# 05_BATTERY.net
KiCad netlist of a schematic drawn in Altium Designer
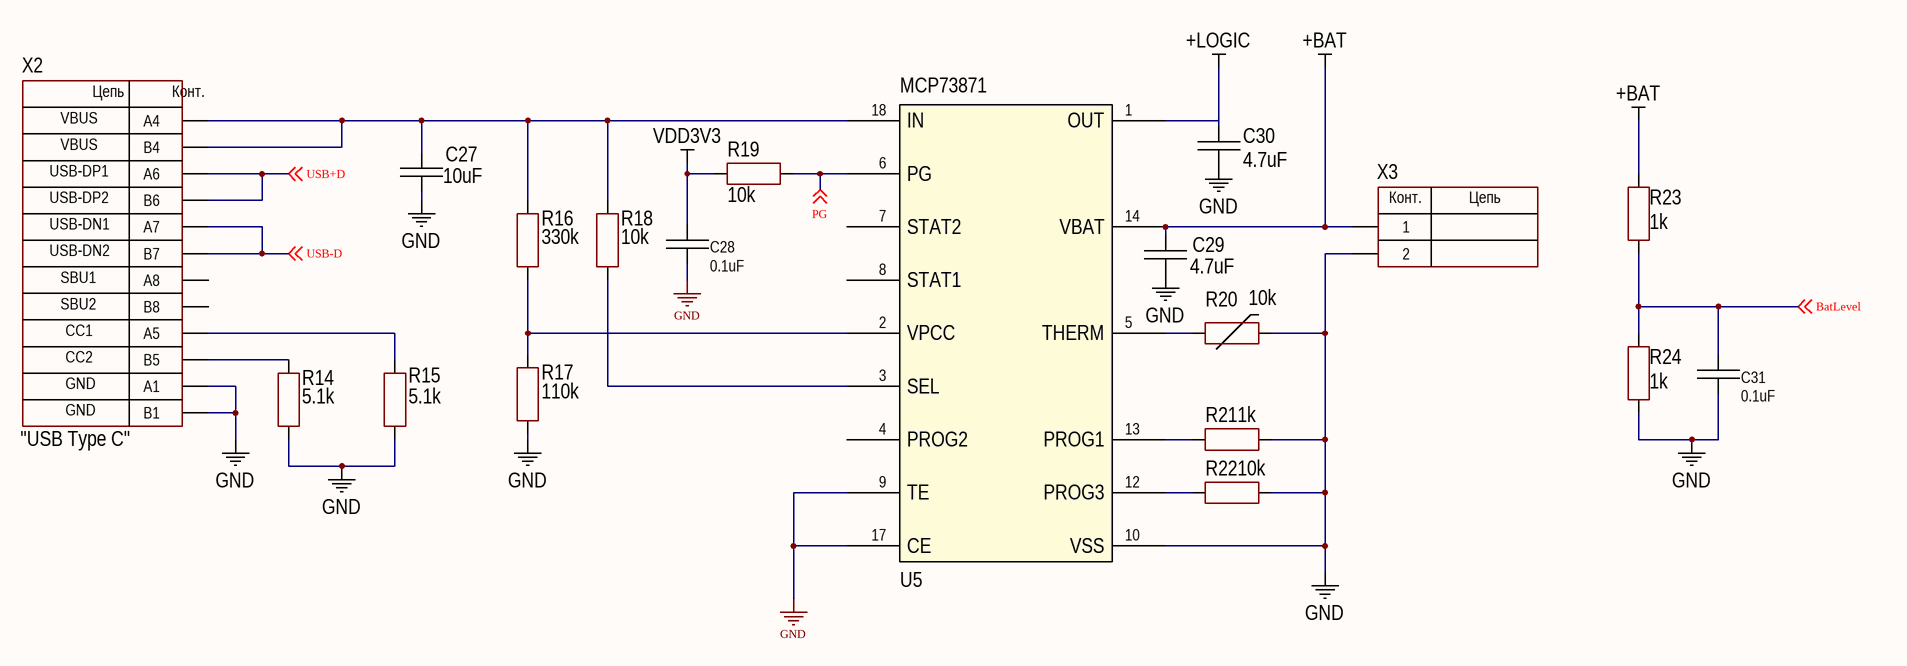
[diagram p0: 05_BATTERY.SchDoc]

(export (version "E")
  (design (tool "Eeschema 10.0.6"))
  (components
    (comp (ref "C27")
      (value "10uF")
      (footprint "CAP: 0805")
      (fields
        (field (name "MANUFACTURER") "Yageo")
        (field (name "PARTNUMBER") "CC0805KRX7R7BB104")
        (field (name "VALUEMANUFACTURERPARTNUMBER") "Ceramic capacitor, 10uF, X7R, ±10%, 16V, 0805, -55...+125°C")
      )
      (libsource (lib "capacitor") (part "Ceramic_0805"))
    )
    (comp (ref "C28")
      (value "0.1uF")
      (footprint "CAP: 0603")
      (fields
        (field (name "MANUFACTURER") "Yageo")
        (field (name "PARTNUMBER") "CC0603KRX7R7BB104")
        (field (name "VALUEMANUFACTURERPARTNUMBER") "Ceramic capacitor, 0.1uF, X7R, ±10%, 16V, 0603, -55...+125°C")
      )
      (libsource (lib "capacitor") (part "Ceramic_0603"))
    )
    (comp (ref "C29")
      (value "4.7uF")
      (footprint "CAP: 0805")
      (fields
        (field (name "MANUFACTURER") "Yageo")
        (field (name "PARTNUMBER") "CC0805KRX7R7BB104")
        (field (name "VALUEMANUFACTURERPARTNUMBER") "Ceramic capacitor, 4.7uF, X7R, ±10%, 16V, 0805, -55...+125°C")
      )
      (libsource (lib "capacitor") (part "Ceramic_0805"))
    )
    (comp (ref "C30")
      (value "4.7uF")
      (footprint "CAP: 0805")
      (fields
        (field (name "MANUFACTURER") "Yageo")
        (field (name "PARTNUMBER") "CC0805KRX7R7BB104")
        (field (name "VALUEMANUFACTURERPARTNUMBER") "Ceramic capacitor, 4.7uF, X7R, ±10%, 16V, 0805, -55...+125°C")
      )
      (libsource (lib "capacitor") (part "Ceramic_0805"))
    )
    (comp (ref "C31")
      (value "0.1uF")
      (footprint "CAP: 0603")
      (fields
        (field (name "MANUFACTURER") "Yageo")
        (field (name "PARTNUMBER") "CC0603KRX7R7BB104")
        (field (name "VALUEMANUFACTURERPARTNUMBER") "Ceramic capacitor, 0.1uF, X7R, ±10%, 16V, 0603, -55...+125°C")
      )
      (libsource (lib "capacitor") (part "Ceramic_0603"))
    )
    (comp (ref "R14")
      (value "5.1k")
      (footprint "RES: 0603")
      (fields
        (field (name "MANUFACTURER") "Yageo")
        (field (name "PARTNUMBER") "RC0603JR-07100RL")
        (field (name "VALUEMANUFACTURERPARTNUMBER") "Resistor film, 5.1k, ±1%, 0603, 0.1W, -55...+125°C")
      )
      (libsource (lib "resistor") (part "Resistor_0603"))
    )
    (comp (ref "R15")
      (value "5.1k")
      (footprint "RES: 0603")
      (fields
        (field (name "MANUFACTURER") "Yageo")
        (field (name "PARTNUMBER") "RC0603JR-07100RL")
        (field (name "VALUEMANUFACTURERPARTNUMBER") "Resistor film, 5.1k, ±1%, 0603, 0.1W, -55...+125°C")
      )
      (libsource (lib "resistor") (part "Resistor_0603"))
    )
    (comp (ref "R16")
      (value "330k")
      (footprint "RES: 0603")
      (fields
        (field (name "MANUFACTURER") "Yageo")
        (field (name "PARTNUMBER") "RC0603JR-07100RL")
        (field (name "VALUEMANUFACTURERPARTNUMBER") "Resistor film, 330k, ±1%, 0603, 0.1W, -55...+125°C")
      )
      (libsource (lib "") (part "Resistor_0603_3"))
    )
    (comp (ref "R17")
      (value "110k")
      (footprint "RES: 0603")
      (fields
        (field (name "MANUFACTURER") "Yageo")
        (field (name "PARTNUMBER") "RC0603JR-07100RL")
        (field (name "VALUEMANUFACTURERPARTNUMBER") "Resistor film, 110k, ±1%, 0603, 0.1W, -55...+125°C")
      )
      (libsource (lib "") (part "Resistor_0603_3"))
    )
    (comp (ref "R18")
      (value "10k")
      (footprint "RES: 0603")
      (fields
        (field (name "MANUFACTURER") "Yageo")
        (field (name "PARTNUMBER") "RC0603JR-07100RL")
        (field (name "VALUEMANUFACTURERPARTNUMBER") "Resistor film, 10k, ±1%, 0603, 0.1W, -55...+125°C")
      )
      (libsource (lib "") (part "Resistor_0603_3"))
    )
    (comp (ref "R19")
      (value "10k")
      (footprint "RES: 0603")
      (fields
        (field (name "MANUFACTURER") "Yageo")
        (field (name "PARTNUMBER") "RC0603JR-07100RL")
        (field (name "VALUEMANUFACTURERPARTNUMBER") "Resistor film, 10k, ±1%, 0603, 0.1W, -55...+125°C")
      )
      (libsource (lib "") (part "Resistor_0603_2"))
    )
    (comp (ref "R20")
      (value "10k")
      (footprint "RES: B57237 (NTC)")
      (fields
        (field (name "MANUFACTURER") "Epcos")
        (field (name "PARTNUMBER") "B57237S229M54")
        (field (name "VALUEMANUFACTURERPARTNUMBER") "NTC resistor, 10k, ±5%, pitch 7.5mm, 7A, -55...+125°C")
      )
      (libsource (lib "resistor") (part "NTC"))
    )
    (comp (ref "R21")
      (value "1k")
      (footprint "RES: 0603")
      (fields
        (field (name "MANUFACTURER") "Yageo")
        (field (name "PARTNUMBER") "RC0603JR-07100RL")
        (field (name "VALUEMANUFACTURERPARTNUMBER") "Resistor film, 1k, ±1%, 0603, 0.1W, -55...+125°C")
      )
      (libsource (lib "") (part "Resistor_0603_1"))
    )
    (comp (ref "R22")
      (value "10k")
      (footprint "RES: 0603")
      (fields
        (field (name "MANUFACTURER") "Yageo")
        (field (name "PARTNUMBER") "RC0603JR-07100RL")
        (field (name "VALUEMANUFACTURERPARTNUMBER") "Resistor film, 10k, ±1%, 0603, 0.1W, -55...+125°C")
      )
      (libsource (lib "") (part "Resistor_0603_1"))
    )
    (comp (ref "R23")
      (value "1k")
      (footprint "RES: 0603")
      (fields
        (field (name "MANUFACTURER") "Yageo")
        (field (name "PARTNUMBER") "RC0603JR-07100RL")
        (field (name "VALUEMANUFACTURERPARTNUMBER") "Resistor film, 1k, ±1%, 0603, 0.1W, -55...+125°C")
      )
      (libsource (lib "resistor") (part "Resistor_0603"))
    )
    (comp (ref "R24")
      (value "1k")
      (footprint "RES: 0603")
      (fields
        (field (name "MANUFACTURER") "Yageo")
        (field (name "PARTNUMBER") "RC0603JR-07100RL")
        (field (name "VALUEMANUFACTURERPARTNUMBER") "Resistor film, 1k, ±1%, 0603, 0.1W, -55...+125°C")
      )
      (libsource (lib "resistor") (part "Resistor_0603"))
    )
    (comp (ref "U5")
      (value "MCP73871")
      (footprint "20-QFN (4x4)")
      (libsource (lib "MyLib") (part "BQ24074RGTT"))
    )
    (comp (ref "X2")
      (value "~")
      (footprint "CON: TYPE-C-31-M-12")
      (fields
        (field (name "MANUFACTURER") "Korean Hroparts")
        (field (name "VALUEMANUFACTURERPARTNUMBER") "USB Type C, 3A")
        (field (name "PARTNUMBER") "TYPE-C-31-M-12")
        (field (name "COMMENTTEXT") "\"USB Type C\"")
      )
      (libsource (lib "connector") (part "Connector_USB_Type_C"))
    )
    (comp (ref "X3")
      (value "~")
      (footprint "CON: CWF-2R")
      (fields
        (field (name "MANUFACTURER") "Connfly")
        (field (name "VALUEMANUFACTURERPARTNUMBER") "Connector, 2pin, 2.54mm, 250VAC, 3A")
        (field (name "PARTNUMBER") "CWF-2R")
      )
      (libsource (lib "connector") (part "CWF-2"))
    )
  )
  (nets
    (net (code "1") (name "+BAT") (class "Default")
      (node (ref "C29") (pin "2") (pinfunction "2_2") (pintype "passive"))
      (node (ref "R23") (pin "1") (pinfunction "1_1") (pintype "passive"))
      (node (ref "U5") (pin "14") (pinfunction "VBAT_14") (pintype "passive"))
      (node (ref "X3") (pin "1") (pinfunction "1_1") (pintype "passive"))
    )
    (net (code "3") (name "+LOGIC") (class "Default")
      (node (ref "C30") (pin "2") (pinfunction "2_2") (pintype "passive"))
      (node (ref "U5") (pin "1") (pinfunction "OUT_1") (pintype "passive"))
    )
    (net (code "4") (name "BatLevel") (class "Default")
      (node (ref "C31") (pin "2") (pinfunction "2_2") (pintype "passive"))
      (node (ref "R23") (pin "2") (pinfunction "2_2") (pintype "passive"))
      (node (ref "R24") (pin "1") (pinfunction "1_1") (pintype "passive"))
    )
    (net (code "5") (name "GND") (class "Default")
      (node (ref "C27") (pin "1") (pinfunction "1_1") (pintype "passive"))
      (node (ref "C28") (pin "1") (pinfunction "1_1") (pintype "passive"))
      (node (ref "C29") (pin "1") (pinfunction "1_1") (pintype "passive"))
      (node (ref "C30") (pin "1") (pinfunction "1_1") (pintype "passive"))
      (node (ref "C31") (pin "1") (pinfunction "1_1") (pintype "passive"))
      (node (ref "R14") (pin "2") (pinfunction "2_2") (pintype "passive"))
      (node (ref "R15") (pin "2") (pinfunction "2_2") (pintype "passive"))
      (node (ref "R17") (pin "1") (pinfunction "1_1") (pintype "passive"))
      (node (ref "R20") (pin "2") (pinfunction "2_2") (pintype "passive"))
      (node (ref "R21") (pin "2") (pinfunction "2_2") (pintype "passive"))
      (node (ref "R22") (pin "2") (pinfunction "2_2") (pintype "passive"))
      (node (ref "R24") (pin "2") (pinfunction "2_2") (pintype "passive"))
      (node (ref "U5") (pin "10") (pinfunction "VSS_10") (pintype "passive"))
      (node (ref "U5") (pin "17") (pinfunction "CE_17") (pintype "passive"))
      (node (ref "U5") (pin "9") (pinfunction "TE_9") (pintype "passive"))
      (node (ref "X2") (pin "A1") (pinfunction "A1_A1") (pintype "power_in"))
      (node (ref "X2") (pin "B1") (pinfunction "B1_B1") (pintype "power_in"))
      (node (ref "X3") (pin "2") (pinfunction "2_2") (pintype "passive"))
    )
    (net (code "6") (name "Net-(R14-Pad1)") (class "Default")
      (node (ref "R14") (pin "1") (pinfunction "1_1") (pintype "passive"))
      (node (ref "X2") (pin "B5") (pinfunction "B5_B5") (pintype "power_in"))
    )
    (net (code "7") (name "Net-(R15-Pad1)") (class "Default")
      (node (ref "R15") (pin "1") (pinfunction "1_1") (pintype "passive"))
      (node (ref "X2") (pin "A5") (pinfunction "A5_A5") (pintype "power_in"))
    )
    (net (code "8") (name "Net-(U5-IN)") (class "Default")
      (node (ref "C27") (pin "2") (pinfunction "2_2") (pintype "passive"))
      (node (ref "R16") (pin "2") (pinfunction "2_2") (pintype "passive"))
      (node (ref "R18") (pin "2") (pinfunction "2_2") (pintype "passive"))
      (node (ref "U5") (pin "18") (pinfunction "IN_18") (pintype "passive"))
      (node (ref "X2") (pin "A4") (pinfunction "A4_A4") (pintype "passive"))
      (node (ref "X2") (pin "B4") (pinfunction "B4_B4") (pintype "passive"))
    )
    (net (code "9") (name "Net-(U5-PROG1)") (class "Default")
      (node (ref "R21") (pin "1") (pinfunction "1_1") (pintype "passive"))
      (node (ref "U5") (pin "13") (pinfunction "PROG1_13") (pintype "passive"))
    )
    (net (code "10") (name "Net-(U5-PROG3)") (class "Default")
      (node (ref "R22") (pin "1") (pinfunction "1_1") (pintype "passive"))
      (node (ref "U5") (pin "12") (pinfunction "PROG3_12") (pintype "passive"))
    )
    (net (code "11") (name "Net-(U5-SEL)") (class "Default")
      (node (ref "R18") (pin "1") (pinfunction "1_1") (pintype "passive"))
      (node (ref "U5") (pin "3") (pinfunction "SEL_3") (pintype "passive"))
    )
    (net (code "12") (name "Net-(U5-THERM)") (class "Default")
      (node (ref "R20") (pin "1") (pinfunction "1_1") (pintype "passive"))
      (node (ref "U5") (pin "5") (pinfunction "THERM_5") (pintype "passive"))
    )
    (net (code "13") (name "Net-(U5-VPCC)") (class "Default")
      (node (ref "R16") (pin "1") (pinfunction "1_1") (pintype "passive"))
      (node (ref "R17") (pin "2") (pinfunction "2_2") (pintype "passive"))
      (node (ref "U5") (pin "2") (pinfunction "VPCC_2") (pintype "passive"))
    )
    (net (code "14") (name "PG") (class "Default")
      (node (ref "R19") (pin "1") (pinfunction "1_1") (pintype "passive"))
      (node (ref "U5") (pin "6") (pinfunction "PG_6") (pintype "passive"))
    )
    (net (code "15") (name "USB+D") (class "Default")
      (node (ref "X2") (pin "A6") (pinfunction "A6_A6") (pintype "power_in"))
      (node (ref "X2") (pin "B6") (pinfunction "B6_B6") (pintype "power_in"))
    )
    (net (code "16") (name "USB-D") (class "Default")
      (node (ref "X2") (pin "A7") (pinfunction "A7_A7") (pintype "power_in"))
      (node (ref "X2") (pin "B7") (pinfunction "B7_B7") (pintype "power_in"))
    )
    (net (code "17") (name "VDD3V3") (class "Default")
      (node (ref "C28") (pin "2") (pinfunction "2_2") (pintype "passive"))
      (node (ref "R19") (pin "2") (pinfunction "2_2") (pintype "passive"))
    )
    (net (code "18") (name "unconnected-(U5-PROG2-Pad4)") (class "Default")
      (node (ref "U5") (pin "4") (pinfunction "PROG2_4") (pintype "passive"))
    )
    (net (code "19") (name "unconnected-(U5-STAT1-Pad8)") (class "Default")
      (node (ref "U5") (pin "8") (pinfunction "STAT1_8") (pintype "passive"))
    )
    (net (code "20") (name "unconnected-(U5-STAT2-Pad7)") (class "Default")
      (node (ref "U5") (pin "7") (pinfunction "STAT2_7") (pintype "passive"))
    )
    (net (code "21") (name "unconnected-(X2-PadA8)") (class "Default")
      (node (ref "X2") (pin "A8") (pinfunction "A8_A8") (pintype "power_in"))
    )
    (net (code "22") (name "unconnected-(X2-PadB8)") (class "Default")
      (node (ref "X2") (pin "B8") (pinfunction "B8_B8") (pintype "power_in"))
    )
  )
)
